# KE04.net
KiCad netlist of a schematic drawn in EAGLE
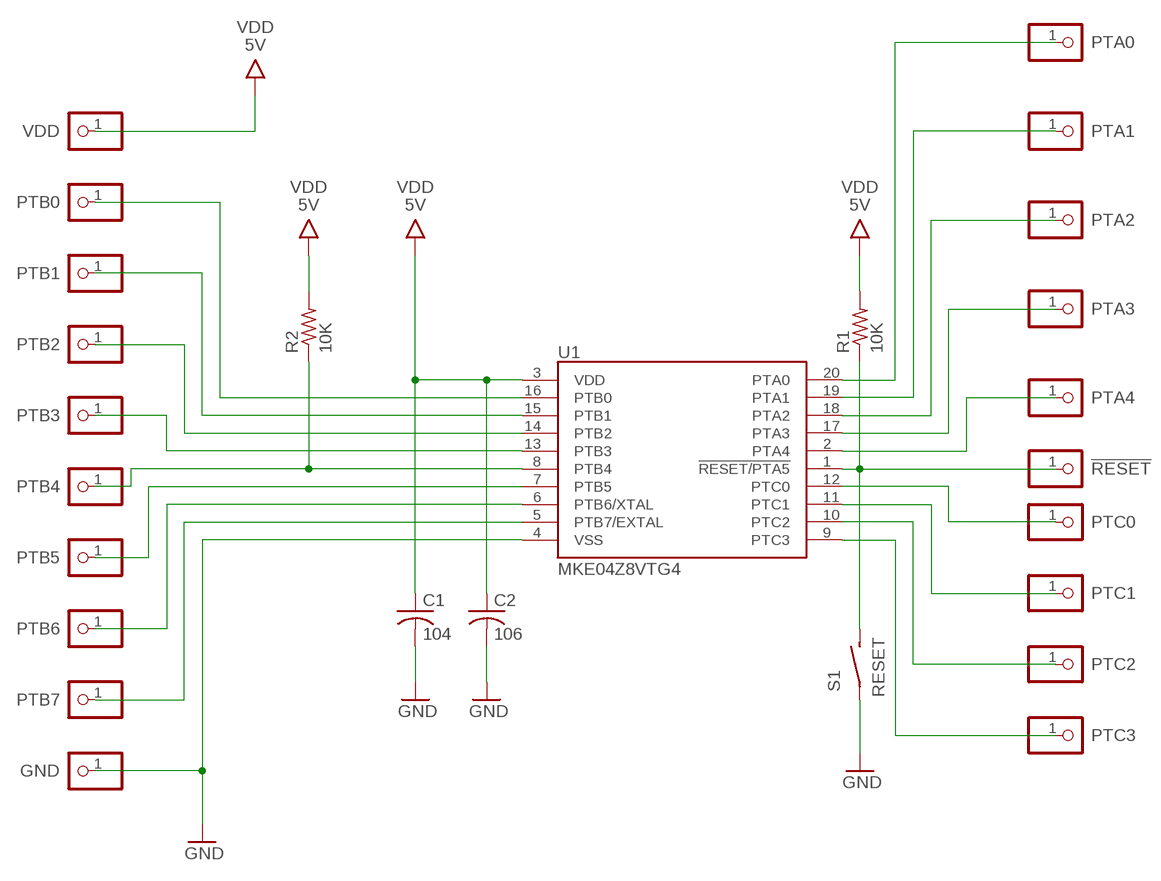
[diagram p0: schematic, sheet 1]

(export (version "E")
  (design (tool "Eeschema 10.0.6"))
  (components
    (comp (ref "C1")
      (value "104")
      (footprint "eagle-import:0603")
      (libsource (lib "eagle-import") (part "C-0603"))
    )
    (comp (ref "C2")
      (value "106")
      (footprint "eagle-import:1206")
      (libsource (lib "eagle-import") (part "C-1206"))
    )
    (comp (ref "JP1")
      (value "!RESET")
      (footprint "eagle-import:1X01-S")
      (libsource (lib "eagle-import") (part "PINHD-1X01_2.54-S"))
    )
    (comp (ref "JP2")
      (value "PTA4")
      (footprint "eagle-import:1X01-S")
      (libsource (lib "eagle-import") (part "PINHD-1X01_2.54-S"))
    )
    (comp (ref "JP3")
      (value "VDD")
      (footprint "eagle-import:1X01-S")
      (libsource (lib "eagle-import") (part "PINHD-1X01_2.54-S"))
    )
    (comp (ref "JP4")
      (value "GND")
      (footprint "eagle-import:1X01-S")
      (libsource (lib "eagle-import") (part "PINHD-1X01_2.54-S"))
    )
    (comp (ref "JP5")
      (value "PTB7")
      (footprint "eagle-import:1X01-S")
      (libsource (lib "eagle-import") (part "PINHD-1X01_2.54-S"))
    )
    (comp (ref "JP6")
      (value "PTB6")
      (footprint "eagle-import:1X01-S")
      (libsource (lib "eagle-import") (part "PINHD-1X01_2.54-S"))
    )
    (comp (ref "JP7")
      (value "PTB5")
      (footprint "eagle-import:1X01-S")
      (libsource (lib "eagle-import") (part "PINHD-1X01_2.54-S"))
    )
    (comp (ref "JP8")
      (value "PTB4")
      (footprint "eagle-import:1X01-S")
      (libsource (lib "eagle-import") (part "PINHD-1X01_2.54-S"))
    )
    (comp (ref "JP9")
      (value "PTC3")
      (footprint "eagle-import:1X01-S")
      (libsource (lib "eagle-import") (part "PINHD-1X01_2.54-S"))
    )
    (comp (ref "JP10")
      (value "PTC2")
      (footprint "eagle-import:1X01-S")
      (libsource (lib "eagle-import") (part "PINHD-1X01_2.54-S"))
    )
    (comp (ref "JP11")
      (value "PTC1")
      (footprint "eagle-import:1X01-S")
      (libsource (lib "eagle-import") (part "PINHD-1X01_2.54-S"))
    )
    (comp (ref "JP12")
      (value "PTC0")
      (footprint "eagle-import:1X01-S")
      (libsource (lib "eagle-import") (part "PINHD-1X01_2.54-S"))
    )
    (comp (ref "JP13")
      (value "PTB3")
      (footprint "eagle-import:1X01-S")
      (libsource (lib "eagle-import") (part "PINHD-1X01_2.54-S"))
    )
    (comp (ref "JP14")
      (value "PTB2")
      (footprint "eagle-import:1X01-S")
      (libsource (lib "eagle-import") (part "PINHD-1X01_2.54-S"))
    )
    (comp (ref "JP15")
      (value "PTB1")
      (footprint "eagle-import:1X01-S")
      (libsource (lib "eagle-import") (part "PINHD-1X01_2.54-S"))
    )
    (comp (ref "JP16")
      (value "PTB0")
      (footprint "eagle-import:1X01-S")
      (libsource (lib "eagle-import") (part "PINHD-1X01_2.54-S"))
    )
    (comp (ref "JP17")
      (value "PTA3")
      (footprint "eagle-import:1X01-S")
      (libsource (lib "eagle-import") (part "PINHD-1X01_2.54-S"))
    )
    (comp (ref "JP18")
      (value "PTA2")
      (footprint "eagle-import:1X01-S")
      (libsource (lib "eagle-import") (part "PINHD-1X01_2.54-S"))
    )
    (comp (ref "JP19")
      (value "PTA1")
      (footprint "eagle-import:1X01-S")
      (libsource (lib "eagle-import") (part "PINHD-1X01_2.54-S"))
    )
    (comp (ref "JP20")
      (value "PTA0")
      (footprint "eagle-import:1X01-S")
      (libsource (lib "eagle-import") (part "PINHD-1X01_2.54-S"))
    )
    (comp (ref "R1")
      (value "10K")
      (footprint "eagle-import:0603")
      (libsource (lib "eagle-import") (part "R0603"))
    )
    (comp (ref "R2")
      (value "10K")
      (footprint "eagle-import:0603")
      (libsource (lib "eagle-import") (part "R0603"))
    )
    (comp (ref "S1")
      (value "RESET")
      (footprint "eagle-import:3X4X2TACT")
      (libsource (lib "eagle-import") (part "SPST_3X4X2"))
    )
    (comp (ref "U1")
      (value "MKE04Z8VTG4")
      (footprint "eagle-import:TSSOP20")
      (libsource (lib "eagle-import") (part "MKE04Z8VTG4"))
    )
  )
  (nets
    (net (code "1") (name "5V") (class "Default")
      (node (ref "C1") (pin "1") (pinfunction "+_1") (pintype "passive"))
      (node (ref "C2") (pin "1") (pinfunction "+_1") (pintype "passive"))
      (node (ref "JP3") (pin "1") (pinfunction "1_1") (pintype "passive"))
      (node (ref "R1") (pin "2") (pinfunction "2_2") (pintype "passive"))
      (node (ref "R2") (pin "2") (pinfunction "2_2") (pintype "passive"))
      (node (ref "U1") (pin "3") (pinfunction "VDD_3") (pintype "bidirectional"))
    )
    (net (code "2") (name "GND") (class "Default")
      (node (ref "C1") (pin "2") (pinfunction "-_2") (pintype "passive"))
      (node (ref "C2") (pin "2") (pinfunction "-_2") (pintype "passive"))
      (node (ref "JP4") (pin "1") (pinfunction "1_1") (pintype "passive"))
      (node (ref "S1") (pin "P$1") (pinfunction "P_P$1") (pintype "passive"))
      (node (ref "U1") (pin "4") (pinfunction "VSS_4") (pintype "bidirectional"))
    )
    (net (code "3") (name "Net-(S1-S)") (class "Default")
      (node (ref "JP1") (pin "1") (pinfunction "1_1") (pintype "passive"))
      (node (ref "R1") (pin "1") (pinfunction "1_1") (pintype "passive"))
      (node (ref "S1") (pin "P$2") (pinfunction "S_P$2") (pintype "passive"))
      (node (ref "U1") (pin "1") (pinfunction "~{RESET/PTA5}_1") (pintype "bidirectional"))
    )
    (net (code "4") (name "Net-(U1-PTA0)") (class "Default")
      (node (ref "JP20") (pin "1") (pinfunction "1_1") (pintype "passive"))
      (node (ref "U1") (pin "20") (pinfunction "PTA0_20") (pintype "bidirectional"))
    )
    (net (code "5") (name "Net-(U1-PTA1)") (class "Default")
      (node (ref "JP19") (pin "1") (pinfunction "1_1") (pintype "passive"))
      (node (ref "U1") (pin "19") (pinfunction "PTA1_19") (pintype "bidirectional"))
    )
    (net (code "6") (name "Net-(U1-PTA2)") (class "Default")
      (node (ref "JP18") (pin "1") (pinfunction "1_1") (pintype "passive"))
      (node (ref "U1") (pin "18") (pinfunction "PTA2_18") (pintype "bidirectional"))
    )
    (net (code "7") (name "Net-(U1-PTA3)") (class "Default")
      (node (ref "JP17") (pin "1") (pinfunction "1_1") (pintype "passive"))
      (node (ref "U1") (pin "17") (pinfunction "PTA3_17") (pintype "bidirectional"))
    )
    (net (code "8") (name "Net-(U1-PTA4)") (class "Default")
      (node (ref "JP2") (pin "1") (pinfunction "1_1") (pintype "passive"))
      (node (ref "U1") (pin "2") (pinfunction "PTA4_2") (pintype "bidirectional"))
    )
    (net (code "9") (name "Net-(U1-PTB0)") (class "Default")
      (node (ref "JP16") (pin "1") (pinfunction "1_1") (pintype "passive"))
      (node (ref "U1") (pin "16") (pinfunction "PTB0_16") (pintype "bidirectional"))
    )
    (net (code "10") (name "Net-(U1-PTB1)") (class "Default")
      (node (ref "JP15") (pin "1") (pinfunction "1_1") (pintype "passive"))
      (node (ref "U1") (pin "15") (pinfunction "PTB1_15") (pintype "bidirectional"))
    )
    (net (code "11") (name "Net-(U1-PTB2)") (class "Default")
      (node (ref "JP14") (pin "1") (pinfunction "1_1") (pintype "passive"))
      (node (ref "U1") (pin "14") (pinfunction "PTB2_14") (pintype "bidirectional"))
    )
    (net (code "12") (name "Net-(U1-PTB3)") (class "Default")
      (node (ref "JP13") (pin "1") (pinfunction "1_1") (pintype "passive"))
      (node (ref "U1") (pin "13") (pinfunction "PTB3_13") (pintype "bidirectional"))
    )
    (net (code "13") (name "Net-(U1-PTB4)") (class "Default")
      (node (ref "JP8") (pin "1") (pinfunction "1_1") (pintype "passive"))
      (node (ref "R2") (pin "1") (pinfunction "1_1") (pintype "passive"))
      (node (ref "U1") (pin "8") (pinfunction "PTB4_8") (pintype "bidirectional"))
    )
    (net (code "14") (name "Net-(U1-PTB5)") (class "Default")
      (node (ref "JP7") (pin "1") (pinfunction "1_1") (pintype "passive"))
      (node (ref "U1") (pin "7") (pinfunction "PTB5_7") (pintype "bidirectional"))
    )
    (net (code "15") (name "Net-(U1-PTB6{slash}XTAL)") (class "Default")
      (node (ref "JP6") (pin "1") (pinfunction "1_1") (pintype "passive"))
      (node (ref "U1") (pin "6") (pinfunction "PTB6/XTAL_6") (pintype "bidirectional"))
    )
    (net (code "16") (name "Net-(U1-PTB7{slash}EXTAL)") (class "Default")
      (node (ref "JP5") (pin "1") (pinfunction "1_1") (pintype "passive"))
      (node (ref "U1") (pin "5") (pinfunction "PTB7/EXTAL_5") (pintype "bidirectional"))
    )
    (net (code "17") (name "Net-(U1-PTC0)") (class "Default")
      (node (ref "JP12") (pin "1") (pinfunction "1_1") (pintype "passive"))
      (node (ref "U1") (pin "12") (pinfunction "PTC0_12") (pintype "bidirectional"))
    )
    (net (code "18") (name "Net-(U1-PTC1)") (class "Default")
      (node (ref "JP11") (pin "1") (pinfunction "1_1") (pintype "passive"))
      (node (ref "U1") (pin "11") (pinfunction "PTC1_11") (pintype "bidirectional"))
    )
    (net (code "19") (name "Net-(U1-PTC2)") (class "Default")
      (node (ref "JP10") (pin "1") (pinfunction "1_1") (pintype "passive"))
      (node (ref "U1") (pin "10") (pinfunction "PTC2_10") (pintype "bidirectional"))
    )
    (net (code "20") (name "Net-(U1-PTC3)") (class "Default")
      (node (ref "JP9") (pin "1") (pinfunction "1_1") (pintype "passive"))
      (node (ref "U1") (pin "9") (pinfunction "PTC3_9") (pintype "bidirectional"))
    )
  )
)
